# ProDoc_Schematic.net
KiCad netlist of a schematic drawn in EasyEDA Pro
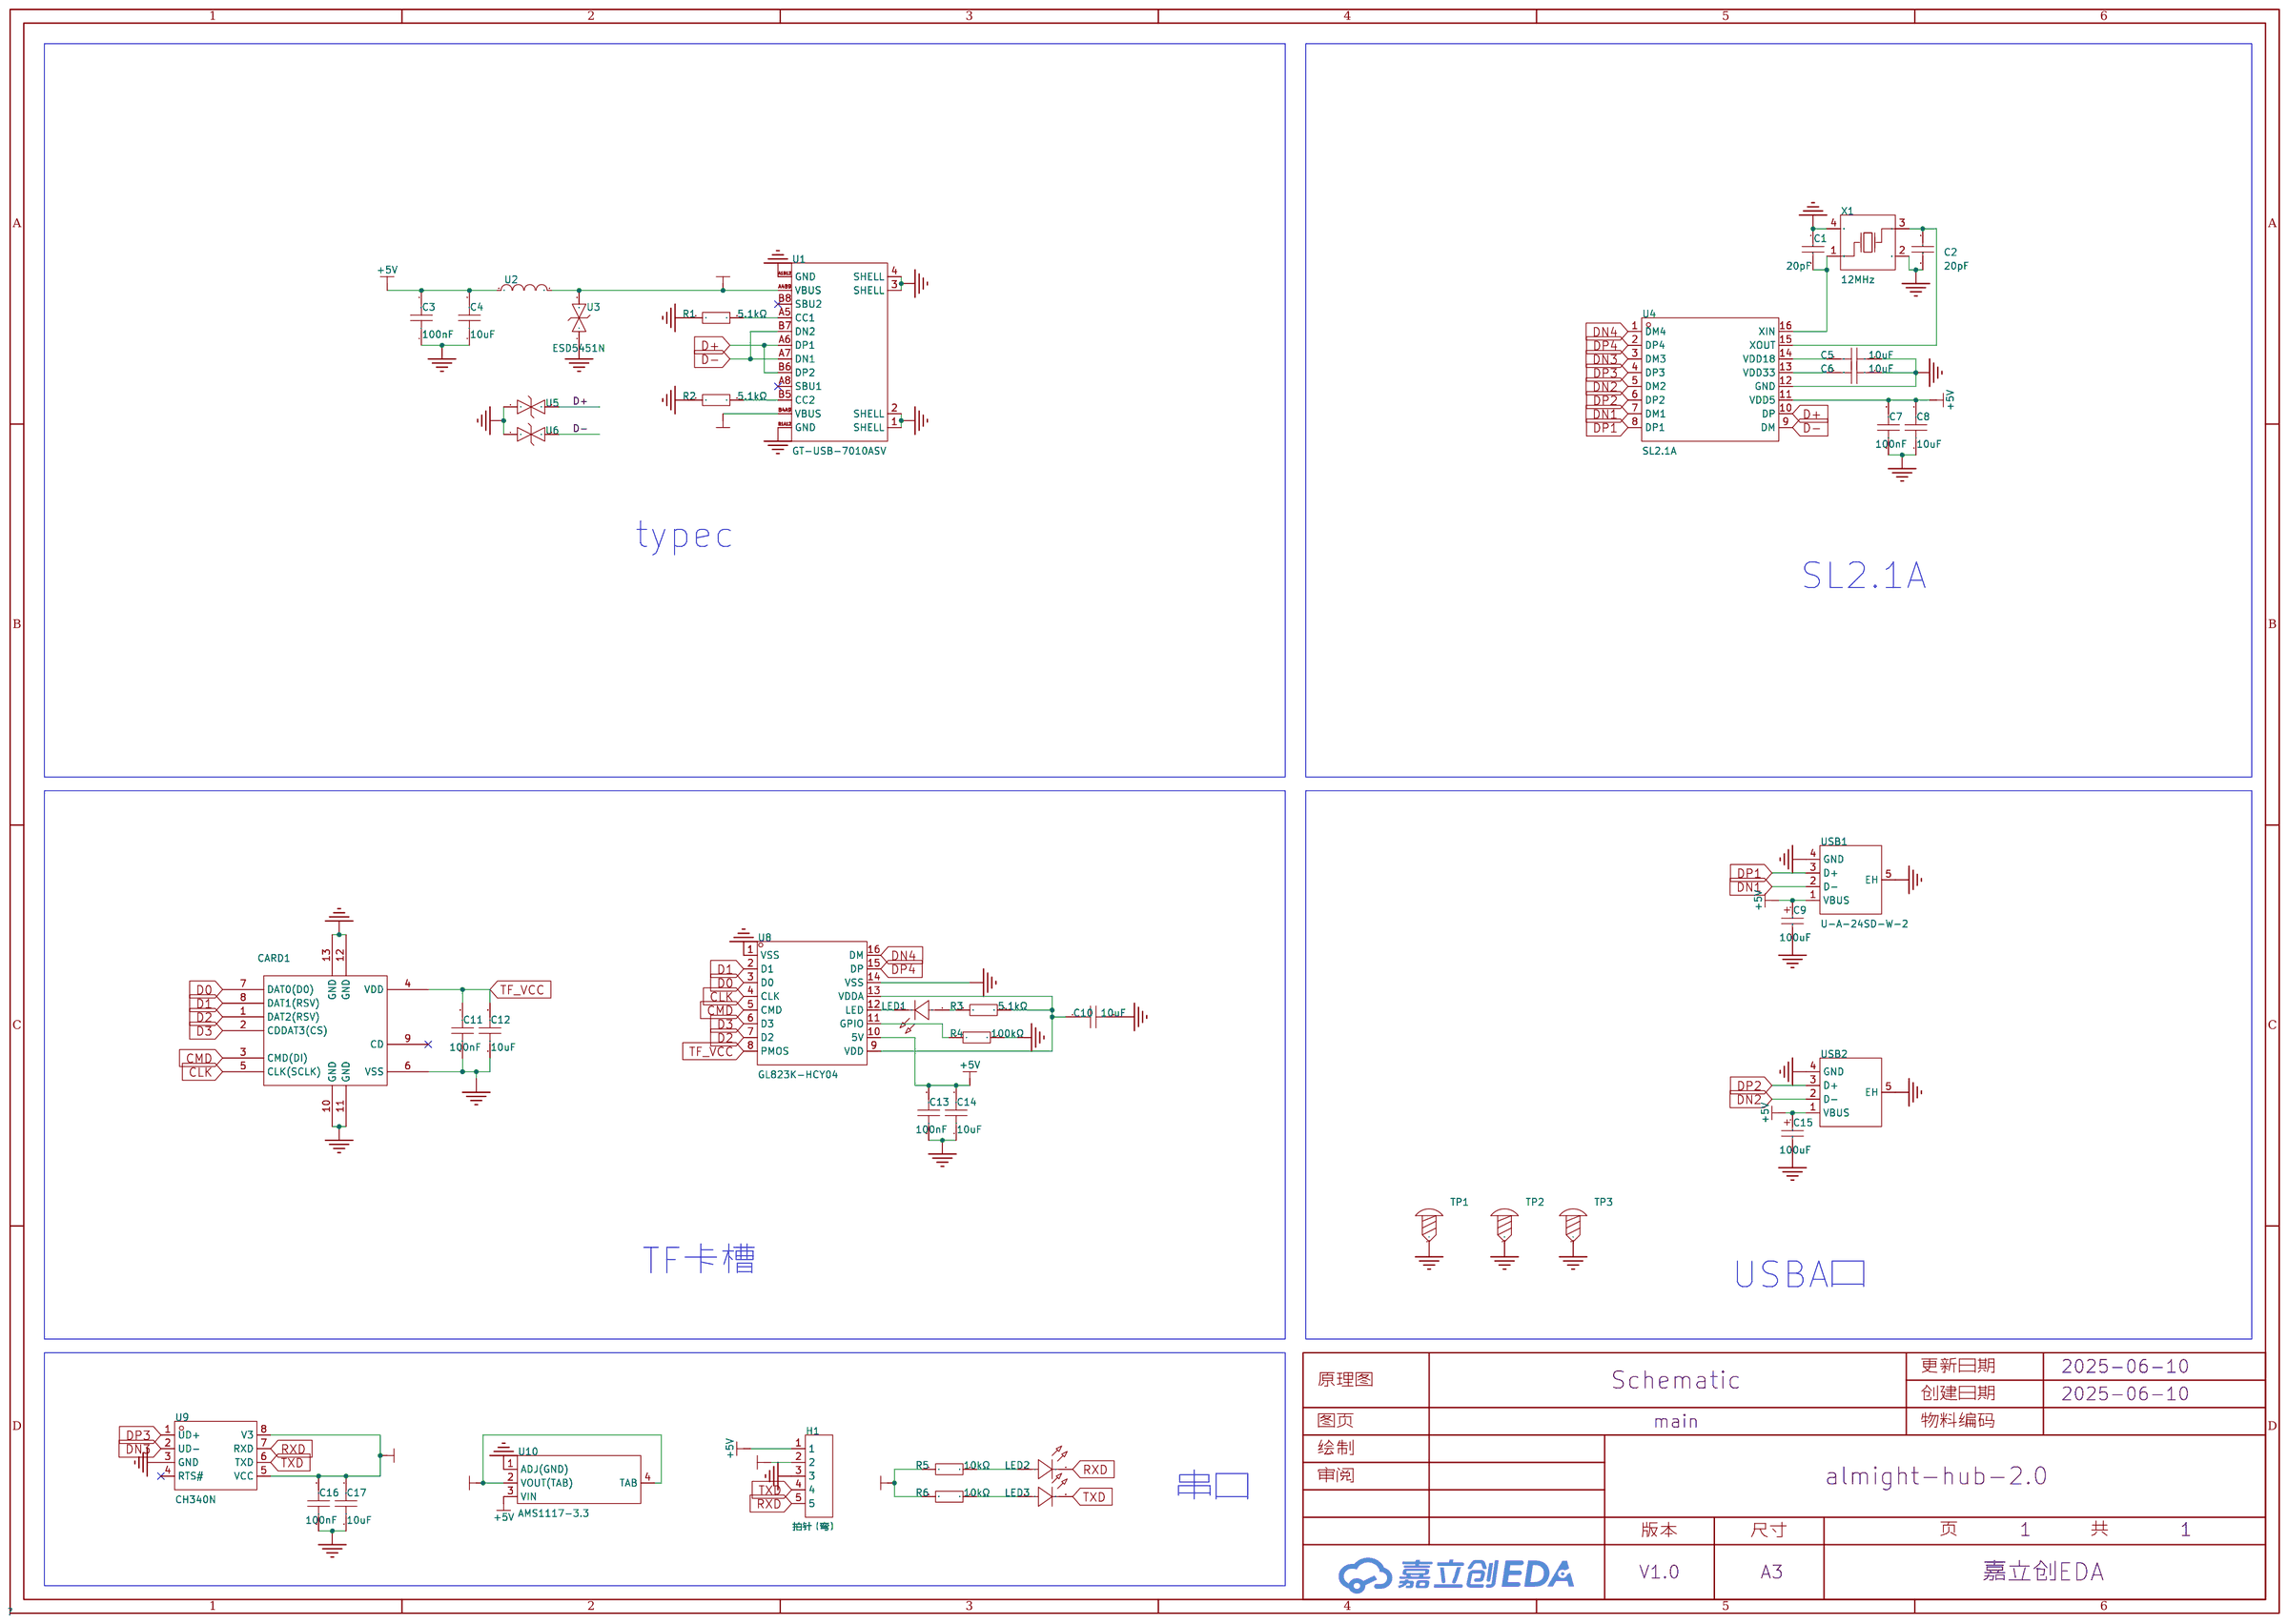
[diagram p0: schematic sheet]

(export (version "E")
  (design (tool "Eeschema 10.0.6"))
  (components
    (comp (ref "C1")
      (value "20pF")
      (footprint "easyedapro:C0402")
      (description "容值:20pF;精度:±5%;额定电压:50V;材质(温度系数):C0G;")
      (fields (field (name "Manufacturer Part") "0402CG200J500NT") (field (name "Manufacturer") "FH(风华)"))
      (libsource (lib "easyedapro") (part "0402CG200J500NT"))
    )
    (comp (ref "C2")
      (value "20pF")
      (footprint "easyedapro:C0402")
      (description "容值:20pF;精度:±5%;额定电压:50V;材质(温度系数):C0G;")
      (fields (field (name "Manufacturer Part") "0402CG200J500NT") (field (name "Manufacturer") "FH(风华)"))
      (libsource (lib "easyedapro") (part "0402CG200J500NT"))
    )
    (comp (ref "C3")
      (value "100nF")
      (footprint "easyedapro:C0402")
      (description "容值:10uF;精度:±20%;额定电压:10V;材质(温度系数):X5R;")
      (fields
        (field (name "Manufacturer Part") "HGC0402R5106M100NTEJ")
        (field (name "Manufacturer") "Chinocera(华瓷)")
      )
      (libsource (lib "easyedapro") (part "HGC0402R5106M100NTEJ"))
    )
    (comp (ref "C4")
      (value "10uF")
      (footprint "easyedapro:C0402")
      (description "容值:10uF;精度:±20%;额定电压:10V;材质(温度系数):X5R;")
      (fields
        (field (name "Manufacturer Part") "HGC0402R5106M100NTEJ")
        (field (name "Manufacturer") "Chinocera(华瓷)")
      )
      (libsource (lib "easyedapro") (part "HGC0402R5106M100NTEJ"))
    )
    (comp (ref "C5")
      (value "10uF")
      (footprint "easyedapro:C0402")
      (description "容值:10uF;精度:±20%;额定电压:10V;材质(温度系数):X5R;")
      (fields
        (field (name "Manufacturer Part") "HGC0402R5106M100NTEJ")
        (field (name "Manufacturer") "Chinocera(华瓷)")
      )
      (libsource (lib "easyedapro") (part "HGC0402R5106M100NTEJ"))
    )
    (comp (ref "C6")
      (value "10uF")
      (footprint "easyedapro:C0402")
      (description "容值:10uF;精度:±20%;额定电压:10V;材质(温度系数):X5R;")
      (fields
        (field (name "Manufacturer Part") "HGC0402R5106M100NTEJ")
        (field (name "Manufacturer") "Chinocera(华瓷)")
      )
      (libsource (lib "easyedapro") (part "HGC0402R5106M100NTEJ"))
    )
    (comp (ref "C7")
      (value "100nF")
      (footprint "easyedapro:C0402")
      (description "容值:10uF;精度:±20%;额定电压:10V;材质(温度系数):X5R;")
      (fields
        (field (name "Manufacturer Part") "HGC0402R5106M100NTEJ")
        (field (name "Manufacturer") "Chinocera(华瓷)")
      )
      (libsource (lib "easyedapro") (part "HGC0402R5106M100NTEJ"))
    )
    (comp (ref "C8")
      (value "10uF")
      (footprint "easyedapro:C0402")
      (description "容值:10uF;精度:±20%;额定电压:10V;材质(温度系数):X5R;")
      (fields
        (field (name "Manufacturer Part") "HGC0402R5106M100NTEJ")
        (field (name "Manufacturer") "Chinocera(华瓷)")
      )
      (libsource (lib "easyedapro") (part "HGC0402R5106M100NTEJ"))
    )
    (comp (ref "C9")
      (value "100uF")
      (footprint "easyedapro:CASE-B_3528")
      (description "容值:100uF;精度:±10%;额定电压:6.3V;等效串联电阻(ESR):1.7Ω@100kHz;")
      (fields (field (name "Manufacturer Part") "TAJB107K006RNJ") (field (name "Manufacturer") "Kyocera AVX"))
      (libsource (lib "easyedapro") (part "TAJB107K006RNJ"))
    )
    (comp (ref "C10")
      (value "10uF")
      (footprint "easyedapro:C0402")
      (description "容值:10uF;精度:±20%;额定电压:10V;材质(温度系数):X5R;")
      (fields
        (field (name "Manufacturer Part") "HGC0402R5106M100NTEJ")
        (field (name "Manufacturer") "Chinocera(华瓷)")
      )
      (libsource (lib "easyedapro") (part "HGC0402R5106M100NTEJ"))
    )
    (comp (ref "C11")
      (value "100nF")
      (footprint "easyedapro:C0402")
      (description "容值:10uF;精度:±20%;额定电压:10V;材质(温度系数):X5R;")
      (fields
        (field (name "Manufacturer Part") "HGC0402R5106M100NTEJ")
        (field (name "Manufacturer") "Chinocera(华瓷)")
      )
      (libsource (lib "easyedapro") (part "HGC0402R5106M100NTEJ"))
    )
    (comp (ref "C12")
      (value "10uF")
      (footprint "easyedapro:C0402")
      (description "容值:10uF;精度:±20%;额定电压:10V;材质(温度系数):X5R;")
      (fields
        (field (name "Manufacturer Part") "HGC0402R5106M100NTEJ")
        (field (name "Manufacturer") "Chinocera(华瓷)")
      )
      (libsource (lib "easyedapro") (part "HGC0402R5106M100NTEJ"))
    )
    (comp (ref "C13")
      (value "100nF")
      (footprint "easyedapro:C0402")
      (description "容值:10uF;精度:±20%;额定电压:10V;材质(温度系数):X5R;")
      (fields
        (field (name "Manufacturer Part") "HGC0402R5106M100NTEJ")
        (field (name "Manufacturer") "Chinocera(华瓷)")
      )
      (libsource (lib "easyedapro") (part "HGC0402R5106M100NTEJ"))
    )
    (comp (ref "C14")
      (value "10uF")
      (footprint "easyedapro:C0402")
      (description "容值:10uF;精度:±20%;额定电压:10V;材质(温度系数):X5R;")
      (fields
        (field (name "Manufacturer Part") "HGC0402R5106M100NTEJ")
        (field (name "Manufacturer") "Chinocera(华瓷)")
      )
      (libsource (lib "easyedapro") (part "HGC0402R5106M100NTEJ"))
    )
    (comp (ref "C15")
      (value "100uF")
      (footprint "easyedapro:CASE-B_3528")
      (description "容值:100uF;精度:±10%;额定电压:6.3V;等效串联电阻(ESR):1.7Ω@100kHz;")
      (fields (field (name "Manufacturer Part") "TAJB107K006RNJ") (field (name "Manufacturer") "Kyocera AVX"))
      (libsource (lib "easyedapro") (part "TAJB107K006RNJ"))
    )
    (comp (ref "C16")
      (value "100nF")
      (footprint "easyedapro:C0402")
      (description "容值:10uF;精度:±20%;额定电压:10V;材质(温度系数):X5R;")
      (fields
        (field (name "Manufacturer Part") "HGC0402R5106M100NTEJ")
        (field (name "Manufacturer") "Chinocera(华瓷)")
      )
      (libsource (lib "easyedapro") (part "HGC0402R5106M100NTEJ"))
    )
    (comp (ref "C17")
      (value "10uF")
      (footprint "easyedapro:C0402")
      (description "容值:10uF;精度:±20%;额定电压:10V;材质(温度系数):X5R;")
      (fields
        (field (name "Manufacturer Part") "HGC0402R5106M100NTEJ")
        (field (name "Manufacturer") "Chinocera(华瓷)")
      )
      (libsource (lib "easyedapro") (part "HGC0402R5106M100NTEJ"))
    )
    (comp (ref "CARD1")
      (value "TF-01A")
      (footprint "easyedapro:TF-SMD_TF-01A")
      (description "卡连接方式:自弹式;卡类型:MicroSD卡(TF卡);连接器类型:卡座;本体最大高度:1.85mm;工作温度范围:-;")
      (fields (field (name "Manufacturer") "韩国韩荣"))
      (libsource (lib "easyedapro") (part "TF-01A"))
    )
    (comp (ref "H1")
      (value "拍针（弯）")
      (footprint "easyedapro:HDR-TH_5P-P2.54-H-M-W10.4")
      (fields (field (name "Manufacturer") "XFCN(兴飞)"))
      (libsource (lib "easyedapro") (part "PZ254R-11-05P"))
    )
    (comp (ref "LED1")
      (value "A-SP192DGHC-C01-4T")
      (footprint "easyedapro:LED0603-FD")
      (fields (field (name "Manufacturer") "Amicc(欧密格光电)"))
      (libsource (lib "easyedapro") (part "A-SP192DGHC-C01-4T"))
    )
    (comp (ref "LED2")
      (value "A-SP192DGHC-C01-4T")
      (footprint "easyedapro:LED0603-FD")
      (fields (field (name "Manufacturer") "Amicc(欧密格光电)"))
      (libsource (lib "easyedapro") (part "A-SP192DGHC-C01-4T"))
    )
    (comp (ref "LED3")
      (value "A-SP192DGHC-C01-4T")
      (footprint "easyedapro:LED0603-FD")
      (fields (field (name "Manufacturer") "Amicc(欧密格光电)"))
      (libsource (lib "easyedapro") (part "A-SP192DGHC-C01-4T"))
    )
    (comp (ref "R1")
      (value "5.1kΩ")
      (footprint "easyedapro:R0402")
      (description "电阻类型:厚膜电阻;阻值:5.1kΩ;精度:±1%;功率:62.5mW;工作电压:50V;温度系数:±100ppm/°C;")
      (fields (field (name "Manufacturer Part") "RC0402FR-075K1L") (field (name "Manufacturer") "YAGEO(国巨)"))
      (libsource (lib "easyedapro") (part "RC0402FR-075K1L"))
    )
    (comp (ref "R2")
      (value "5.1kΩ")
      (footprint "easyedapro:R0402")
      (description "电阻类型:厚膜电阻;阻值:5.1kΩ;精度:±1%;功率:62.5mW;工作电压:50V;温度系数:±100ppm/°C;")
      (fields (field (name "Manufacturer Part") "RC0402FR-075K1L") (field (name "Manufacturer") "YAGEO(国巨)"))
      (libsource (lib "easyedapro") (part "RC0402FR-075K1L"))
    )
    (comp (ref "R3")
      (value "5.1kΩ")
      (footprint "easyedapro:R0402")
      (description "电阻类型:厚膜电阻;阻值:5.1kΩ;精度:±1%;功率:62.5mW;工作电压:50V;温度系数:±100ppm/°C;")
      (fields (field (name "Manufacturer Part") "RC0402FR-075K1L") (field (name "Manufacturer") "YAGEO(国巨)"))
      (libsource (lib "easyedapro") (part "RC0402FR-075K1L"))
    )
    (comp (ref "R4")
      (value "100kΩ")
      (footprint "easyedapro:R0402")
      (description "电阻类型:厚膜电阻;阻值:5.1kΩ;精度:±1%;功率:62.5mW;工作电压:50V;温度系数:±100ppm/°C;")
      (fields (field (name "Manufacturer Part") "RC0402FR-075K1L") (field (name "Manufacturer") "YAGEO(国巨)"))
      (libsource (lib "easyedapro") (part "RC0402FR-075K1L"))
    )
    (comp (ref "R5")
      (value "10kΩ")
      (footprint "easyedapro:R0402")
      (description "电阻类型:厚膜电阻;阻值:5.1kΩ;精度:±1%;功率:62.5mW;工作电压:50V;温度系数:±100ppm/°C;")
      (fields (field (name "Manufacturer Part") "RC0402FR-075K1L") (field (name "Manufacturer") "YAGEO(国巨)"))
      (libsource (lib "easyedapro") (part "RC0402FR-075K1L"))
    )
    (comp (ref "R6")
      (value "10kΩ")
      (footprint "easyedapro:R0402")
      (description "电阻类型:厚膜电阻;阻值:5.1kΩ;精度:±1%;功率:62.5mW;工作电压:50V;温度系数:±100ppm/°C;")
      (fields (field (name "Manufacturer Part") "RC0402FR-075K1L") (field (name "Manufacturer") "YAGEO(国巨)"))
      (libsource (lib "easyedapro") (part "RC0402FR-075K1L"))
    )
    (comp (ref "TP1") (value "~") (footprint "easyedapro:M1螺丝孔") (libsource (lib "easyedapro") (part "螺丝孔")))
    (comp (ref "TP2") (value "~") (footprint "easyedapro:M1螺丝孔") (libsource (lib "easyedapro") (part "螺丝孔")))
    (comp (ref "TP3") (value "~") (footprint "easyedapro:M1螺丝孔") (libsource (lib "easyedapro") (part "螺丝孔")))
    (comp (ref "U1")
      (value "GT-USB-7010ASV")
      (footprint "easyedapro:USB-C-SMD_G-SWITCH_GT-USB-7010ASV")
      (description "连接器类型:Type-C;标准:USB 2.0;公母:母;安装方式:卧贴;触点数量:16P;端口数量:1;额定电流 - 电源:3A;工作温度范围:-40°C~+85°C;")
      (fields (field (name "Manufacturer") "G-Switch(品赞)"))
      (libsource (lib "easyedapro") (part "GT-USB-7010ASV"))
    )
    (comp (ref "U2")
      (value "UPZ1608U221-2R2TF")
      (footprint "easyedapro:L0603")
      (description "标称阻抗@测试频率:220Ω@100MHz;误差:±25%;直流电阻(RDC):50mΩ;")
      (fields (field (name "Manufacturer") "Sunlord(顺络)"))
      (libsource (lib "easyedapro") (part "UPZ1608U221-2R2TF"))
    )
    (comp (ref "U3")
      (value "ESD5451N")
      (footprint "easyedapro:DFN1006-2L-BI")
      (description "极性:双向;反向截止电压(Vrwm):5V;最大钳位电压:9.8V;峰值脉冲电流(Ipp):9A;击穿电压:8V;")
      (fields (field (name "Manufacturer") "HXY MOSFET(华轩阳电子)"))
      (libsource (lib "easyedapro") (part "ESD5451N_C5261080"))
    )
    (comp (ref "U4")
      (value "SL2.1A")
      (footprint "easyedapro:SOP-16_L10.0-W3.9-P1.27-LS6.0-BL")
      (description "SL2.1A是一颗高集成度,高性能,低功耗的USB2.0集线器主控芯片，支持USB2.0高速(480MHz),全速(12MHz)和低速模式(1.5MHz)，内置12MHz晶体振荡器。")
      (fields (field (name "Manufacturer") "CoreChips(和芯润德)"))
      (libsource (lib "easyedapro") (part "SL2.1A"))
    )
    (comp (ref "U5")
      (value "ESD5451N")
      (footprint "easyedapro:DFN1006-2L-BI")
      (description "极性:双向;反向截止电压(Vrwm):5V;最大钳位电压:9.8V;峰值脉冲电流(Ipp):9A;击穿电压:8V;")
      (fields (field (name "Manufacturer") "HXY MOSFET(华轩阳电子)"))
      (libsource (lib "easyedapro") (part "ESD5451N_C5261080"))
    )
    (comp (ref "U6")
      (value "ESD5451N")
      (footprint "easyedapro:DFN1006-2L-BI")
      (description "极性:双向;反向截止电压(Vrwm):5V;最大钳位电压:9.8V;峰值脉冲电流(Ipp):9A;击穿电压:8V;")
      (fields (field (name "Manufacturer") "HXY MOSFET(华轩阳电子)"))
      (libsource (lib "easyedapro") (part "ESD5451N_C5261080"))
    )
    (comp (ref "U8")
      (value "GL823K-HCY04")
      (footprint "easyedapro:SSOP-16_L4.9-W3.9-P0.64-LS6.0-BL")
      (description "应用功能:-;接口协议:-;")
      (fields (field (name "Manufacturer") "GENESYS(创惟)"))
      (libsource (lib "easyedapro") (part "GL823K-HCY04"))
    )
    (comp (ref "U9")
      (value "CH340N")
      (footprint "easyedapro:SOP-8_L5.0-W4.0-P1.27-LS6.0-BL")
      (description "应用功能:USB转串口;接口协议:USB 2.0;通道数:-;数据速率:2Mbps;")
      (fields (field (name "Manufacturer") "WCH(南京沁恒)"))
      (libsource (lib "easyedapro") (part "CH340N"))
    )
    (comp (ref "U10")
      (value "AMS1117-3.3")
      (footprint "easyedapro:SOT-223-4_L6.5-W3.5-P2.30-LS7.0-BR")
      (description "输出类型:固定;工作电压:12V;输出电压:3.3V;输出电流:1A;电源纹波抑制比(PSRR):60dB@(120Hz);输出极性:正极;")
      (fields (field (name "Manufacturer") "UMW(友台半导体)"))
      (libsource (lib "easyedapro") (part "AMS1117-3.3_C347222"))
    )
    (comp (ref "USB1")
      (value "U-A-24SD-W-2")
      (footprint "easyedapro:USB-A-SMD_U-A-24SD-W-2")
      (description "连接器类型:Type-A;标准:USB 2.0;公母:母;端口数量:1;触点数量:4P;安装方式:沉板;额定电流 - 电源:1.5A;工作温度范围:-;")
      (fields (field (name "Manufacturer") "韩国韩荣"))
      (libsource (lib "easyedapro") (part "U-A-24SD-W-2"))
    )
    (comp (ref "USB2")
      (value "U-A-24SD-W-2")
      (footprint "easyedapro:USB-A-SMD_U-A-24SD-W-2")
      (description "连接器类型:Type-A;标准:USB 2.0;公母:母;端口数量:1;触点数量:4P;安装方式:沉板;额定电流 - 电源:1.5A;工作温度范围:-;")
      (fields (field (name "Manufacturer") "韩国韩荣"))
      (libsource (lib "easyedapro") (part "U-A-24SD-W-2"))
    )
    (comp (ref "X1")
      (value "12MHz")
      (footprint "easyedapro:CRYSTAL-SMD_4P-L3.2-W2.5-BL")
      (description "晶振类型:贴片晶振;频率:12MHz;常温频差:±10ppm;外接负载电容:20pF;频率稳定度(全温):±20ppm;")
      (fields (field (name "Manufacturer Part") "X322512MSB4SI") (field (name "Manufacturer") "YXC(扬兴晶振)"))
      (libsource (lib "easyedapro") (part "X322512MSB4SI"))
    )
  )
  (nets
    (net (code "1") (name "+5V") (class "Default")
      (node (ref "C13") (pin "2") (pinfunction "2_2") (pintype "unspecified"))
      (node (ref "C14") (pin "2") (pinfunction "2_2") (pintype "unspecified"))
      (node (ref "C15") (pin "1") (pinfunction "1_1") (pintype "input"))
      (node (ref "C3") (pin "2") (pinfunction "2_2") (pintype "unspecified"))
      (node (ref "C4") (pin "2") (pinfunction "2_2") (pintype "unspecified"))
      (node (ref "C7") (pin "2") (pinfunction "2_2") (pintype "unspecified"))
      (node (ref "C8") (pin "2") (pinfunction "2_2") (pintype "unspecified"))
      (node (ref "C9") (pin "1") (pinfunction "1_1") (pintype "input"))
      (node (ref "H1") (pin "1") (pinfunction "1_1") (pintype "unspecified"))
      (node (ref "U10") (pin "3") (pinfunction "VIN_3") (pintype "unspecified"))
      (node (ref "U2") (pin "1") (pinfunction "1_1") (pintype "unspecified"))
      (node (ref "U4") (pin "11") (pinfunction "VDD5_11") (pintype "unspecified"))
      (node (ref "U8") (pin "10") (pinfunction "5V_10") (pintype "unspecified"))
      (node (ref "USB1") (pin "1") (pinfunction "VBUS_1") (pintype "unspecified"))
      (node (ref "USB2") (pin "1") (pinfunction "VBUS_1") (pintype "unspecified"))
    )
    (net (code "2") (name "3V3") (class "Default")
      (node (ref "C16") (pin "2") (pinfunction "2_2") (pintype "unspecified"))
      (node (ref "C17") (pin "2") (pinfunction "2_2") (pintype "unspecified"))
      (node (ref "H1") (pin "2") (pinfunction "2_2") (pintype "unspecified"))
      (node (ref "R5") (pin "1") (pinfunction "1_1") (pintype "input"))
      (node (ref "R6") (pin "1") (pinfunction "1_1") (pintype "input"))
      (node (ref "U10") (pin "2") (pinfunction "VOUT(TAB)_2") (pintype "unspecified"))
      (node (ref "U10") (pin "4") (pinfunction "TAB_4") (pintype "unspecified"))
      (node (ref "U9") (pin "5") (pinfunction "VCC_5") (pintype "unspecified"))
      (node (ref "U9") (pin "8") (pinfunction "V3_8") (pintype "unspecified"))
    )
    (net (code "3") (name "CLK") (class "Default")
      (node (ref "CARD1") (pin "5") (pinfunction "CLK(SCLK)_5") (pintype "input"))
      (node (ref "U8") (pin "4") (pinfunction "CLK_4") (pintype "unspecified"))
    )
    (net (code "4") (name "CMD") (class "Default")
      (node (ref "CARD1") (pin "3") (pinfunction "CMD(DI)_3") (pintype "input"))
      (node (ref "U8") (pin "5") (pinfunction "CMD_5") (pintype "unspecified"))
    )
    (net (code "5") (name "D+") (class "Default")
      (node (ref "U1") (pin "A6") (pinfunction "DP1_A6") (pintype "unspecified"))
      (node (ref "U1") (pin "B6") (pinfunction "DP2_B6") (pintype "unspecified"))
      (node (ref "U4") (pin "10") (pinfunction "DP_10") (pintype "unspecified"))
      (node (ref "U5") (pin "2") (pinfunction "2_2") (pintype "unspecified"))
    )
    (net (code "6") (name "D-") (class "Default")
      (node (ref "U1") (pin "A7") (pinfunction "DN1_A7") (pintype "unspecified"))
      (node (ref "U1") (pin "B7") (pinfunction "DN2_B7") (pintype "unspecified"))
      (node (ref "U4") (pin "9") (pinfunction "DM_9") (pintype "unspecified"))
      (node (ref "U6") (pin "2") (pinfunction "2_2") (pintype "unspecified"))
    )
    (net (code "7") (name "D0") (class "Default")
      (node (ref "CARD1") (pin "7") (pinfunction "DAT0(D0)_7") (pintype "bidirectional"))
      (node (ref "U8") (pin "3") (pinfunction "D0_3") (pintype "unspecified"))
    )
    (net (code "8") (name "D1") (class "Default")
      (node (ref "CARD1") (pin "8") (pinfunction "DAT1(RSV)_8") (pintype "bidirectional"))
      (node (ref "U8") (pin "2") (pinfunction "D1_2") (pintype "unspecified"))
    )
    (net (code "9") (name "D2") (class "Default")
      (node (ref "CARD1") (pin "1") (pinfunction "DAT2(RSV)_1") (pintype "bidirectional"))
      (node (ref "U8") (pin "7") (pinfunction "D2_7") (pintype "unspecified"))
    )
    (net (code "10") (name "D3") (class "Default")
      (node (ref "CARD1") (pin "2") (pinfunction "CDDAT3(CS)_2") (pintype "bidirectional"))
      (node (ref "U8") (pin "6") (pinfunction "D3_6") (pintype "unspecified"))
    )
    (net (code "11") (name "DN1") (class "Default")
      (node (ref "U4") (pin "7") (pinfunction "DM1_7") (pintype "unspecified"))
      (node (ref "USB1") (pin "2") (pinfunction "D-_2") (pintype "unspecified"))
    )
    (net (code "12") (name "DN2") (class "Default")
      (node (ref "U4") (pin "5") (pinfunction "DM2_5") (pintype "unspecified"))
      (node (ref "USB2") (pin "2") (pinfunction "D-_2") (pintype "unspecified"))
    )
    (net (code "13") (name "DN3") (class "Default")
      (node (ref "U4") (pin "3") (pinfunction "DM3_3") (pintype "unspecified"))
      (node (ref "U9") (pin "2") (pinfunction "UD-_2") (pintype "unspecified"))
    )
    (net (code "14") (name "DN4") (class "Default")
      (node (ref "U4") (pin "1") (pinfunction "DM4_1") (pintype "unspecified"))
      (node (ref "U8") (pin "16") (pinfunction "DM_16") (pintype "unspecified"))
    )
    (net (code "15") (name "DP1") (class "Default")
      (node (ref "U4") (pin "8") (pinfunction "DP1_8") (pintype "unspecified"))
      (node (ref "USB1") (pin "3") (pinfunction "D+_3") (pintype "unspecified"))
    )
    (net (code "16") (name "DP2") (class "Default")
      (node (ref "U4") (pin "6") (pinfunction "DP2_6") (pintype "unspecified"))
      (node (ref "USB2") (pin "3") (pinfunction "D+_3") (pintype "unspecified"))
    )
    (net (code "17") (name "DP3") (class "Default")
      (node (ref "U4") (pin "4") (pinfunction "DP3_4") (pintype "unspecified"))
      (node (ref "U9") (pin "1") (pinfunction "UD+_1") (pintype "unspecified"))
    )
    (net (code "18") (name "DP4") (class "Default")
      (node (ref "U4") (pin "2") (pinfunction "DP4_2") (pintype "unspecified"))
      (node (ref "U8") (pin "15") (pinfunction "DP_15") (pintype "unspecified"))
    )
    (net (code "19") (name "GND") (class "Default")
      (node (ref "C1") (pin "1") (pinfunction "1_1") (pintype "input"))
      (node (ref "C10") (pin "2") (pinfunction "2_2") (pintype "unspecified"))
      (node (ref "C11") (pin "1") (pinfunction "1_1") (pintype "unspecified"))
      (node (ref "C12") (pin "1") (pinfunction "1_1") (pintype "unspecified"))
      (node (ref "C13") (pin "1") (pinfunction "1_1") (pintype "unspecified"))
      (node (ref "C14") (pin "1") (pinfunction "1_1") (pintype "unspecified"))
      (node (ref "C15") (pin "2") (pinfunction "2_2") (pintype "input"))
      (node (ref "C16") (pin "1") (pinfunction "1_1") (pintype "unspecified"))
      (node (ref "C17") (pin "1") (pinfunction "1_1") (pintype "unspecified"))
      (node (ref "C2") (pin "2") (pinfunction "2_2") (pintype "input"))
      (node (ref "C3") (pin "1") (pinfunction "1_1") (pintype "unspecified"))
      (node (ref "C4") (pin "1") (pinfunction "1_1") (pintype "unspecified"))
      (node (ref "C5") (pin "1") (pinfunction "1_1") (pintype "unspecified"))
      (node (ref "C6") (pin "1") (pinfunction "1_1") (pintype "unspecified"))
      (node (ref "C7") (pin "1") (pinfunction "1_1") (pintype "unspecified"))
      (node (ref "C8") (pin "1") (pinfunction "1_1") (pintype "unspecified"))
      (node (ref "C9") (pin "2") (pinfunction "2_2") (pintype "input"))
      (node (ref "CARD1") (pin "10") (pinfunction "GND_10") (pintype "input"))
      (node (ref "CARD1") (pin "11") (pinfunction "GND_11") (pintype "input"))
      (node (ref "CARD1") (pin "12") (pinfunction "GND_12") (pintype "input"))
      (node (ref "CARD1") (pin "13") (pinfunction "GND_13") (pintype "input"))
      (node (ref "CARD1") (pin "6") (pinfunction "VSS_6") (pintype "input"))
      (node (ref "H1") (pin "3") (pinfunction "3_3") (pintype "unspecified"))
      (node (ref "R1") (pin "1") (pinfunction "1_1") (pintype "input"))
      (node (ref "R2") (pin "1") (pinfunction "1_1") (pintype "input"))
      (node (ref "R4") (pin "2") (pinfunction "2_2") (pintype "input"))
      (node (ref "TP1") (pin "1") (pinfunction "1_1") (pintype "input"))
      (node (ref "TP2") (pin "1") (pinfunction "1_1") (pintype "input"))
      (node (ref "TP3") (pin "1") (pinfunction "1_1") (pintype "input"))
      (node (ref "U1") (pin "1") (pinfunction "SHELL_1") (pintype "unspecified"))
      (node (ref "U1") (pin "2") (pinfunction "SHELL_2") (pintype "unspecified"))
      (node (ref "U1") (pin "3") (pinfunction "SHELL_3") (pintype "unspecified"))
      (node (ref "U1") (pin "4") (pinfunction "SHELL_4") (pintype "unspecified"))
      (node (ref "U1") (pin "A1B12") (pinfunction "GND_A1B12") (pintype "unspecified"))
      (node (ref "U1") (pin "B1A12") (pinfunction "GND_B1A12") (pintype "unspecified"))
      (node (ref "U10") (pin "1") (pinfunction "ADJ(GND)_1") (pintype "unspecified"))
      (node (ref "U3") (pin "1") (pinfunction "1_1") (pintype "unspecified"))
      (node (ref "U4") (pin "12") (pinfunction "GND_12") (pintype "unspecified"))
      (node (ref "U5") (pin "1") (pinfunction "1_1") (pintype "unspecified"))
      (node (ref "U6") (pin "1") (pinfunction "1_1") (pintype "unspecified"))
      (node (ref "U8") (pin "1") (pinfunction "VSS_1") (pintype "unspecified"))
      (node (ref "U8") (pin "14") (pinfunction "VSS_14") (pintype "unspecified"))
      (node (ref "U9") (pin "3") (pinfunction "GND_3") (pintype "unspecified"))
      (node (ref "USB1") (pin "4") (pinfunction "GND_4") (pintype "unspecified"))
      (node (ref "USB1") (pin "5") (pinfunction "EH_5") (pintype "unspecified"))
      (node (ref "USB2") (pin "4") (pinfunction "GND_4") (pintype "unspecified"))
      (node (ref "USB2") (pin "5") (pinfunction "EH_5") (pintype "unspecified"))
      (node (ref "X1") (pin "2") (pinfunction "GND_2") (pintype "unspecified"))
      (node (ref "X1") (pin "4") (pinfunction "GND_4") (pintype "unspecified"))
    )
    (net (code "20") (name "Net-(LED1-A)") (class "Default")
      (node (ref "LED1") (pin "1") (pinfunction "A_1") (pintype "unspecified"))
      (node (ref "R3") (pin "1") (pinfunction "1_1") (pintype "input"))
    )
    (net (code "21") (name "Net-(LED1-K)") (class "Default")
      (node (ref "LED1") (pin "2") (pinfunction "K_2") (pintype "unspecified"))
      (node (ref "U8") (pin "12") (pinfunction "LED_12") (pintype "unspecified"))
    )
    (net (code "22") (name "Net-(LED2-A)") (class "Default")
      (node (ref "LED2") (pin "1") (pinfunction "A_1") (pintype "unspecified"))
      (node (ref "R5") (pin "2") (pinfunction "2_2") (pintype "input"))
    )
    (net (code "23") (name "Net-(LED3-A)") (class "Default")
      (node (ref "LED3") (pin "1") (pinfunction "A_1") (pintype "unspecified"))
      (node (ref "R6") (pin "2") (pinfunction "2_2") (pintype "input"))
    )
    (net (code "24") (name "Net-(U1-CC1)") (class "Default")
      (node (ref "R1") (pin "2") (pinfunction "2_2") (pintype "input"))
      (node (ref "U1") (pin "A5") (pinfunction "CC1_A5") (pintype "unspecified"))
    )
    (net (code "25") (name "Net-(U1-CC2)") (class "Default")
      (node (ref "R2") (pin "2") (pinfunction "2_2") (pintype "input"))
      (node (ref "U1") (pin "B5") (pinfunction "CC2_B5") (pintype "unspecified"))
    )
    (net (code "26") (name "Net-(U4-VDD18)") (class "Default")
      (node (ref "C5") (pin "2") (pinfunction "2_2") (pintype "unspecified"))
      (node (ref "U4") (pin "14") (pinfunction "VDD18_14") (pintype "unspecified"))
    )
    (net (code "27") (name "Net-(U4-VDD33)") (class "Default")
      (node (ref "C6") (pin "2") (pinfunction "2_2") (pintype "unspecified"))
      (node (ref "U4") (pin "13") (pinfunction "VDD33_13") (pintype "unspecified"))
    )
    (net (code "28") (name "Net-(U4-XIN)") (class "Default")
      (node (ref "C1") (pin "2") (pinfunction "2_2") (pintype "input"))
      (node (ref "U4") (pin "16") (pinfunction "XIN_16") (pintype "unspecified"))
      (node (ref "X1") (pin "1") (pinfunction "OSC1_1") (pintype "unspecified"))
    )
    (net (code "29") (name "Net-(U4-XOUT)") (class "Default")
      (node (ref "C2") (pin "1") (pinfunction "1_1") (pintype "input"))
      (node (ref "U4") (pin "15") (pinfunction "XOUT_15") (pintype "unspecified"))
      (node (ref "X1") (pin "3") (pinfunction "OSC2_3") (pintype "unspecified"))
    )
    (net (code "30") (name "Net-(U8-GPIO)") (class "Default")
      (node (ref "R4") (pin "1") (pinfunction "1_1") (pintype "input"))
      (node (ref "U8") (pin "11") (pinfunction "GPIO_11") (pintype "unspecified"))
    )
    (net (code "31") (name "Net-(U8-VDD)") (class "Default")
      (node (ref "C10") (pin "1") (pinfunction "1_1") (pintype "unspecified"))
      (node (ref "R3") (pin "2") (pinfunction "2_2") (pintype "input"))
      (node (ref "U8") (pin "13") (pinfunction "VDDA_13") (pintype "unspecified"))
      (node (ref "U8") (pin "9") (pinfunction "VDD_9") (pintype "unspecified"))
    )
    (net (code "32") (name "RXD") (class "Default")
      (node (ref "H1") (pin "5") (pinfunction "5_5") (pintype "unspecified"))
      (node (ref "LED2") (pin "2") (pinfunction "K_2") (pintype "unspecified"))
      (node (ref "U9") (pin "7") (pinfunction "RXD_7") (pintype "unspecified"))
    )
    (net (code "33") (name "TF_VCC") (class "Default")
      (node (ref "C11") (pin "2") (pinfunction "2_2") (pintype "unspecified"))
      (node (ref "C12") (pin "2") (pinfunction "2_2") (pintype "unspecified"))
      (node (ref "CARD1") (pin "4") (pinfunction "VDD_4") (pintype "input"))
      (node (ref "U8") (pin "8") (pinfunction "PMOS_8") (pintype "unspecified"))
    )
    (net (code "34") (name "TXD") (class "Default")
      (node (ref "H1") (pin "4") (pinfunction "4_4") (pintype "unspecified"))
      (node (ref "LED3") (pin "2") (pinfunction "K_2") (pintype "unspecified"))
      (node (ref "U9") (pin "6") (pinfunction "TXD_6") (pintype "unspecified"))
    )
    (net (code "35") (name "VBUS") (class "Default")
      (node (ref "U1") (pin "A4B9") (pinfunction "VBUS_A4B9") (pintype "unspecified"))
      (node (ref "U1") (pin "B4A9") (pinfunction "VBUS_B4A9") (pintype "unspecified"))
      (node (ref "U2") (pin "2") (pinfunction "2_2") (pintype "unspecified"))
      (node (ref "U3") (pin "2") (pinfunction "2_2") (pintype "unspecified"))
    )
    (net (code "36") (name "unconnected-(CARD1-CD-Pad9)") (class "Default")
      (node (ref "CARD1") (pin "9") (pinfunction "CD_9") (pintype "input+no_connect"))
    )
    (net (code "37") (name "unconnected-(U1-SBU1-PadA8)") (class "Default")
      (node (ref "U1") (pin "A8") (pinfunction "SBU1_A8") (pintype "unspecified+no_connect"))
    )
    (net (code "38") (name "unconnected-(U1-SBU2-PadB8)") (class "Default")
      (node (ref "U1") (pin "B8") (pinfunction "SBU2_B8") (pintype "unspecified+no_connect"))
    )
    (net (code "39") (name "unconnected-(U9-RTS#-Pad4)") (class "Default")
      (node (ref "U9") (pin "4") (pinfunction "RTS#_4") (pintype "unspecified+no_connect"))
    )
  )
)
